# GPS_IMU_SENSORS.net
KiCad netlist of a schematic drawn in Altium Designer
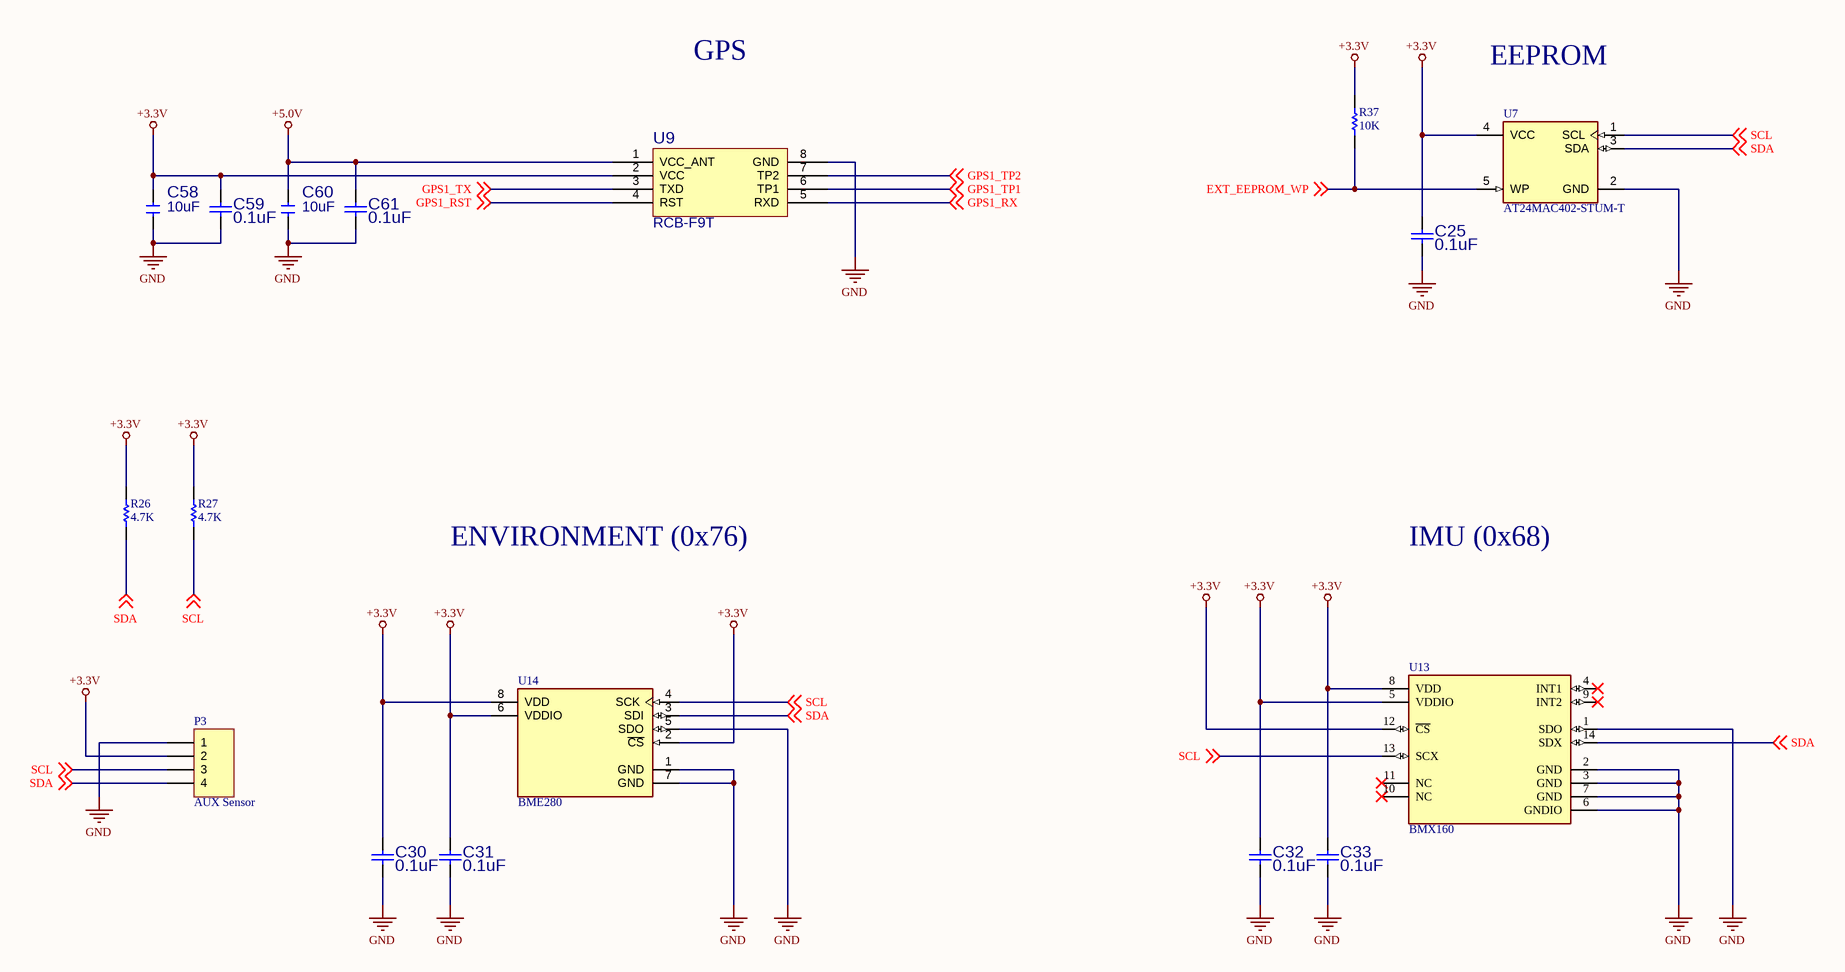
[diagram p0: GPS_IMU_SENSORS.SchDoc]

(export (version "E")
  (design (tool "Eeschema 10.0.6"))
  (components
    (comp (ref "C25")
      (value "0.1uF")
      (footprint "CAPC1608X87X45ML20T05")
      (description "C0603X104K5RACAUTO")
      (fields (field (name "MANUFACTURER") "Kemet"))
      (libsource (lib "Altium Content Vault") (part "CAP"))
    )
    (comp (ref "C30")
      (value "0.1uF")
      (footprint "CAPC1608X87X45ML20T05")
      (description "C0603X104K5RACAUTO")
      (fields (field (name "MANUFACTURER") "Kemet"))
      (libsource (lib "Altium Content Vault") (part "CAP"))
    )
    (comp (ref "C31")
      (value "0.1uF")
      (footprint "CAPC1608X87X45ML20T05")
      (description "C0603X104K5RACAUTO")
      (fields (field (name "MANUFACTURER") "Kemet"))
      (libsource (lib "Altium Content Vault") (part "CAP"))
    )
    (comp (ref "C32")
      (value "0.1uF")
      (footprint "CAPC1608X87X45ML20T05")
      (description "C0603X104K5RACAUTO")
      (fields (field (name "MANUFACTURER") "Kemet"))
      (libsource (lib "Altium Content Vault") (part "CAP"))
    )
    (comp (ref "C33")
      (value "0.1uF")
      (footprint "CAPC1608X87X45ML20T05")
      (description "C0603X104K5RACAUTO")
      (fields (field (name "MANUFACTURER") "Kemet"))
      (libsource (lib "Altium Content Vault") (part "CAP"))
    )
    (comp (ref "C58")
      (value "10uF")
      (footprint "CAPC2012X14N")
      (description "CAP, CER, 10.UF, 25V, 10%, X5R, 0805")
      (fields
        (field (name "MFG PART NUM") "TMK212BBJ106KG-T")
        (field (name "VALENTIUM PART NUM") "<VALENTIUM>")
      )
      (libsource (lib "Capacitors") (part "CAP_0805_10UF_25V"))
    )
    (comp (ref "C59")
      (value "0.1uF")
      (footprint "CAPC1608X87X45ML20T05")
      (description "C0603X104K5RACAUTO")
      (fields (field (name "MANUFACTURER") "Kemet"))
      (libsource (lib "Altium Content Vault") (part "CAP"))
    )
    (comp (ref "C60")
      (value "10uF")
      (footprint "CAPC2012X14N")
      (description "CAP, CER, 10.UF, 25V, 10%, X5R, 0805")
      (fields
        (field (name "MFG PART NUM") "TMK212BBJ106KG-T")
        (field (name "VALENTIUM PART NUM") "<VALENTIUM>")
      )
      (libsource (lib "Capacitors") (part "CAP_0805_10UF_25V"))
    )
    (comp (ref "C61")
      (value "0.1uF")
      (footprint "CAPC1608X87X45ML20T05")
      (description "C0603X104K5RACAUTO")
      (fields (field (name "MANUFACTURER") "Kemet"))
      (libsource (lib "Altium Content Vault") (part "CAP"))
    )
    (comp (ref "P3")
      (value "AUX Sensor")
      (footprint "HDR1X4")
      (description "Header, 4-Pin")
      (fields (field (name "PUBLISHER") "Altium Limited"))
      (libsource (lib "Miscellaneous Connectors") (part "Header 4"))
    )
    (comp (ref "R26")
      (value "4.7K")
      (footprint "RESC1608X55X30NL15T15")
      (fields (field (name "TOLERANCE") "5%"))
      (libsource (lib "Altium Content Vault") (part "RES-2"))
    )
    (comp (ref "R27")
      (value "4.7K")
      (footprint "RESC1608X55X30NL15T15")
      (fields (field (name "TOLERANCE") "5%"))
      (libsource (lib "Altium Content Vault") (part "RES-2"))
    )
    (comp (ref "R37")
      (value "10K")
      (footprint "RESC1608X55X30LL15T20")
      (fields (field (name "TOLERANCE") "±1%") (field (name "MANUFACTURER") "Stackpole-Electronics-Inc."))
      (libsource (lib "Altium Content Vault") (part "RES-2"))
    )
    (comp (ref "U7")
      (value "AT24MAC402-STUM-T")
      (footprint "FP-5TS1-IPC_C")
      (description "IC EEPROM 2K I2C 1MHZ SOT23-5")
      (fields
        (field (name "MANUFACTURER") "Microchip")
        (field (name "OCTOPART") "https://octopart.com/at24mac402-stum-t-microchip-77758112")
      )
      (libsource (lib "Altium Content Vault") (part "93fe34f5f049140596bab6421a6454b"))
    )
    (comp (ref "U9")
      (value "RCB-F9T")
      (footprint "GNSS")
      (description "MOD, GPS")
      (fields (field (name "VELENTIUM PART NUM") "<V PART NUM>"))
      (libsource (lib "Modules") (part "RCB-F9T"))
    )
    (comp (ref "U13")
      (value "BMX160")
      (footprint "FP-BMX160-MFG")
      (description "IMU ACCEL/GYRO/MAG")
      (libsource (lib "Altium Content Vault") (part "34da024cb04dfcb8cf696aa13940ccc"))
    )
    (comp (ref "U14")
      (value "BME280")
      (footprint "FP-BME280-MFG")
      (description "SENSOR PRESSURE HUMIDITY TEMP")
      (libsource (lib "Altium Content Vault") (part "d58e2f6669bc67e6a2bc6a28610ca79"))
    )
  )
  (nets
    (net (code "1") (name "+3.3V") (class "Default")
      (node (ref "C25") (pin "2") (pinfunction "2_2") (pintype "passive"))
      (node (ref "C30") (pin "2") (pinfunction "2_2") (pintype "passive"))
      (node (ref "C31") (pin "2") (pinfunction "2_2") (pintype "passive"))
      (node (ref "C32") (pin "2") (pinfunction "2_2") (pintype "passive"))
      (node (ref "C33") (pin "2") (pinfunction "2_2") (pintype "passive"))
      (node (ref "C58") (pin "1") (pinfunction "1_1") (pintype "passive"))
      (node (ref "C59") (pin "2") (pinfunction "2_2") (pintype "passive"))
      (node (ref "P3") (pin "2") (pinfunction "2_2") (pintype "passive"))
      (node (ref "R26") (pin "2") (pinfunction "2_2") (pintype "passive"))
      (node (ref "R27") (pin "2") (pinfunction "2_2") (pintype "passive"))
      (node (ref "R37") (pin "2") (pinfunction "2_2") (pintype "passive"))
      (node (ref "U13") (pin "12") (pinfunction "~{CS}_12") (pintype "bidirectional"))
      (node (ref "U13") (pin "5") (pinfunction "VDDIO_5") (pintype "power_in"))
      (node (ref "U13") (pin "8") (pinfunction "VDD_8") (pintype "power_in"))
      (node (ref "U14") (pin "2") (pinfunction "~{CS}_2") (pintype "input"))
      (node (ref "U14") (pin "6") (pinfunction "VDDIO_6") (pintype "power_in"))
      (node (ref "U14") (pin "8") (pinfunction "VDD_8") (pintype "power_in"))
      (node (ref "U7") (pin "4") (pinfunction "VCC_4") (pintype "power_in"))
      (node (ref "U9") (pin "2") (pinfunction "VCC_2") (pintype "passive"))
    )
    (net (code "2") (name "+5.0V") (class "Default")
      (node (ref "C60") (pin "1") (pinfunction "1_1") (pintype "passive"))
      (node (ref "C61") (pin "2") (pinfunction "2_2") (pintype "passive"))
      (node (ref "U9") (pin "1") (pinfunction "VCC_ANT_1") (pintype "passive"))
    )
    (net (code "3") (name "EXT_EEPROM_WP") (class "Default")
      (node (ref "R37") (pin "1") (pinfunction "1_1") (pintype "passive"))
      (node (ref "U7") (pin "5") (pinfunction "WP_5") (pintype "input"))
    )
    (net (code "4") (name "GND") (class "Default")
      (node (ref "C25") (pin "1") (pinfunction "1_1") (pintype "passive"))
      (node (ref "C30") (pin "1") (pinfunction "1_1") (pintype "passive"))
      (node (ref "C31") (pin "1") (pinfunction "1_1") (pintype "passive"))
      (node (ref "C32") (pin "1") (pinfunction "1_1") (pintype "passive"))
      (node (ref "C33") (pin "1") (pinfunction "1_1") (pintype "passive"))
      (node (ref "C58") (pin "2") (pinfunction "2_2") (pintype "passive"))
      (node (ref "C59") (pin "1") (pinfunction "1_1") (pintype "passive"))
      (node (ref "C60") (pin "2") (pinfunction "2_2") (pintype "passive"))
      (node (ref "C61") (pin "1") (pinfunction "1_1") (pintype "passive"))
      (node (ref "P3") (pin "1") (pinfunction "1_1") (pintype "passive"))
      (node (ref "U13") (pin "1") (pinfunction "SDO_1") (pintype "bidirectional"))
      (node (ref "U13") (pin "2") (pinfunction "GND_2") (pintype "power_in"))
      (node (ref "U13") (pin "3") (pinfunction "GND_3") (pintype "power_in"))
      (node (ref "U13") (pin "6") (pinfunction "GNDIO_6") (pintype "power_in"))
      (node (ref "U13") (pin "7") (pinfunction "GND_7") (pintype "power_in"))
      (node (ref "U14") (pin "1") (pinfunction "GND_1") (pintype "power_in"))
      (node (ref "U14") (pin "5") (pinfunction "SDO_5") (pintype "bidirectional"))
      (node (ref "U14") (pin "7") (pinfunction "GND_7") (pintype "power_in"))
      (node (ref "U7") (pin "2") (pinfunction "GND_2") (pintype "power_in"))
      (node (ref "U9") (pin "8") (pinfunction "GND_8") (pintype "passive"))
    )
    (net (code "5") (name "GPS1_RST") (class "Default")
      (node (ref "U9") (pin "4") (pinfunction "RST_4") (pintype "passive"))
    )
    (net (code "6") (name "GPS1_RX") (class "Default")
      (node (ref "U9") (pin "5") (pinfunction "RXD_5") (pintype "passive"))
    )
    (net (code "7") (name "GPS1_TP1") (class "Default")
      (node (ref "U9") (pin "6") (pinfunction "TP1_6") (pintype "passive"))
    )
    (net (code "8") (name "GPS1_TP2") (class "Default")
      (node (ref "U9") (pin "7") (pinfunction "TP2_7") (pintype "passive"))
    )
    (net (code "9") (name "GPS1_TX") (class "Default")
      (node (ref "U9") (pin "3") (pinfunction "TXD_3") (pintype "passive"))
    )
    (net (code "10") (name "SCL") (class "Default")
      (node (ref "P3") (pin "3") (pinfunction "3_3") (pintype "passive"))
      (node (ref "R27") (pin "1") (pinfunction "1_1") (pintype "passive"))
      (node (ref "U13") (pin "13") (pinfunction "SCX_13") (pintype "bidirectional"))
      (node (ref "U14") (pin "4") (pinfunction "SCK_4") (pintype "input"))
      (node (ref "U7") (pin "1") (pinfunction "SCL_1") (pintype "input"))
    )
    (net (code "11") (name "SDA") (class "Default")
      (node (ref "P3") (pin "4") (pinfunction "4_4") (pintype "passive"))
      (node (ref "R26") (pin "1") (pinfunction "1_1") (pintype "passive"))
      (node (ref "U13") (pin "14") (pinfunction "SDX_14") (pintype "bidirectional"))
      (node (ref "U14") (pin "3") (pinfunction "SDI_3") (pintype "bidirectional"))
      (node (ref "U7") (pin "3") (pinfunction "SDA_3") (pintype "bidirectional"))
    )
    (net (code "12") (name "unconnected-(U13-INT1-Pad4)") (class "Default")
      (node (ref "U13") (pin "4") (pinfunction "INT1_4") (pintype "bidirectional+no_connect"))
    )
    (net (code "13") (name "unconnected-(U13-INT2-Pad9)") (class "Default")
      (node (ref "U13") (pin "9") (pinfunction "INT2_9") (pintype "bidirectional+no_connect"))
    )
    (net (code "14") (name "unconnected-(U13-NC-Pad10)") (class "Default")
      (node (ref "U13") (pin "10") (pinfunction "NC_10") (pintype "passive+no_connect"))
    )
    (net (code "15") (name "unconnected-(U13-NC-Pad11)") (class "Default")
      (node (ref "U13") (pin "11") (pinfunction "NC_11") (pintype "passive+no_connect"))
    )
  )
)
